# capSwitch.net
KiCad netlist of a schematic drawn in EAGLE
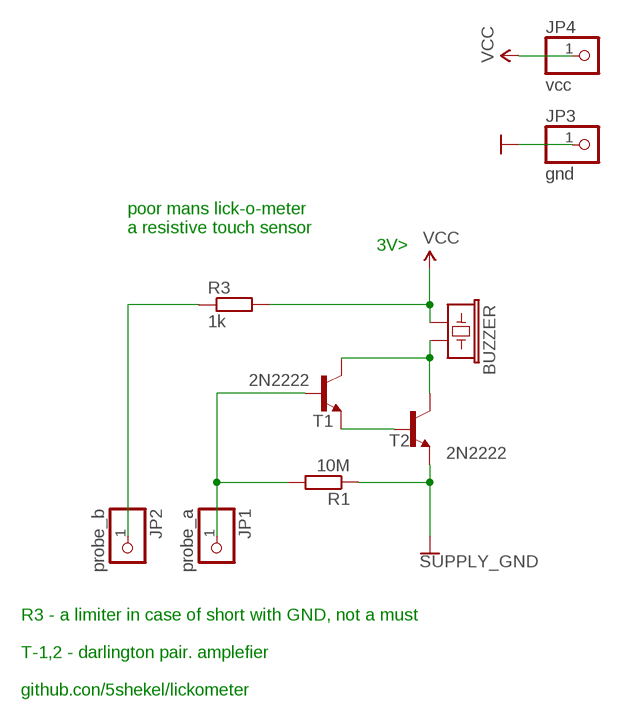
[diagram p0: schematic, sheet 1]

(export (version "E")
  (design (tool "Eeschema 10.0.6"))
  (components
    (comp (ref "BUZZER")
      (value "BUZZERSMD2-KIT")
      (footprint "eagle-import:BUZZER-CCV-KIT")
      (libsource (lib "eagle-import") (part "BUZZERSMD2-KIT"))
    )
    (comp (ref "JP1")
      (value "probe_a")
      (footprint "eagle-import:1X01_OVAL")
      (libsource (lib "eagle-import") (part "HEADER-1X1"))
    )
    (comp (ref "JP2")
      (value "probe_b")
      (footprint "eagle-import:1X01_OVAL")
      (libsource (lib "eagle-import") (part "HEADER-1X1"))
    )
    (comp (ref "JP3")
      (value "gnd")
      (footprint "eagle-import:1X01_OVAL")
      (libsource (lib "eagle-import") (part "HEADER-1X1"))
    )
    (comp (ref "JP4")
      (value "vcc")
      (footprint "eagle-import:1X01_OVAL")
      (libsource (lib "eagle-import") (part "HEADER-1X1"))
    )
    (comp (ref "R1")
      (value "10M")
      (footprint "eagle-import:RTH025W")
      (libsource (lib "eagle-import") (part "RESISTOR-PTH-0.4"))
    )
    (comp (ref "R3")
      (value "1k")
      (footprint "eagle-import:RTH025W")
      (libsource (lib "eagle-import") (part "RESISTOR-PTH-0.4"))
    )
    (comp (ref "T1")
      (value "2N2222")
      (footprint "eagle-import:TO92-EBC-OVAL")
      (libsource (lib "eagle-import") (part "2N2222"))
    )
    (comp (ref "T2")
      (value "2N2222")
      (footprint "eagle-import:TO92-EBC-OVAL")
      (libsource (lib "eagle-import") (part "2N2222"))
    )
  )
  (nets
    (net (code "1") (name "Net-(BUZZER-2)") (class "Default")
      (node (ref "BUZZER") (pin "-") (pinfunction "2_-") (pintype "passive"))
      (node (ref "T1") (pin "C") (pinfunction "C_C") (pintype "passive"))
      (node (ref "T2") (pin "C") (pinfunction "C_C") (pintype "passive"))
    )
    (net (code "2") (name "Net-(JP1-Pad1)") (class "Default")
      (node (ref "JP1") (pin "1") (pinfunction "1_1") (pintype "passive"))
      (node (ref "R1") (pin "2") (pinfunction "2_2") (pintype "passive"))
      (node (ref "T1") (pin "B") (pinfunction "B_B") (pintype "passive"))
    )
    (net (code "3") (name "Net-(JP2-Pad1)") (class "Default")
      (node (ref "JP2") (pin "1") (pinfunction "1_1") (pintype "passive"))
      (node (ref "R3") (pin "1") (pinfunction "1_1") (pintype "passive"))
    )
    (net (code "4") (name "Net-(T1-PadE)") (class "Default")
      (node (ref "T1") (pin "E") (pinfunction "E_E") (pintype "passive"))
      (node (ref "T2") (pin "B") (pinfunction "B_B") (pintype "passive"))
    )
    (net (code "5") (name "SUPPLY_GND") (class "Default")
      (node (ref "JP3") (pin "1") (pinfunction "1_1") (pintype "passive"))
      (node (ref "R1") (pin "1") (pinfunction "1_1") (pintype "passive"))
      (node (ref "T2") (pin "E") (pinfunction "E_E") (pintype "passive"))
    )
    (net (code "6") (name "VCC") (class "Default")
      (node (ref "BUZZER") (pin "+") (pinfunction "1_+") (pintype "passive"))
      (node (ref "JP4") (pin "1") (pinfunction "1_1") (pintype "passive"))
      (node (ref "R3") (pin "2") (pinfunction "2_2") (pintype "passive"))
    )
  )
)
